# SCH_RP2350_Ucompute2_Rev1_1_2025-11-06.net
KiCad netlist of a schematic drawn in EasyEDA
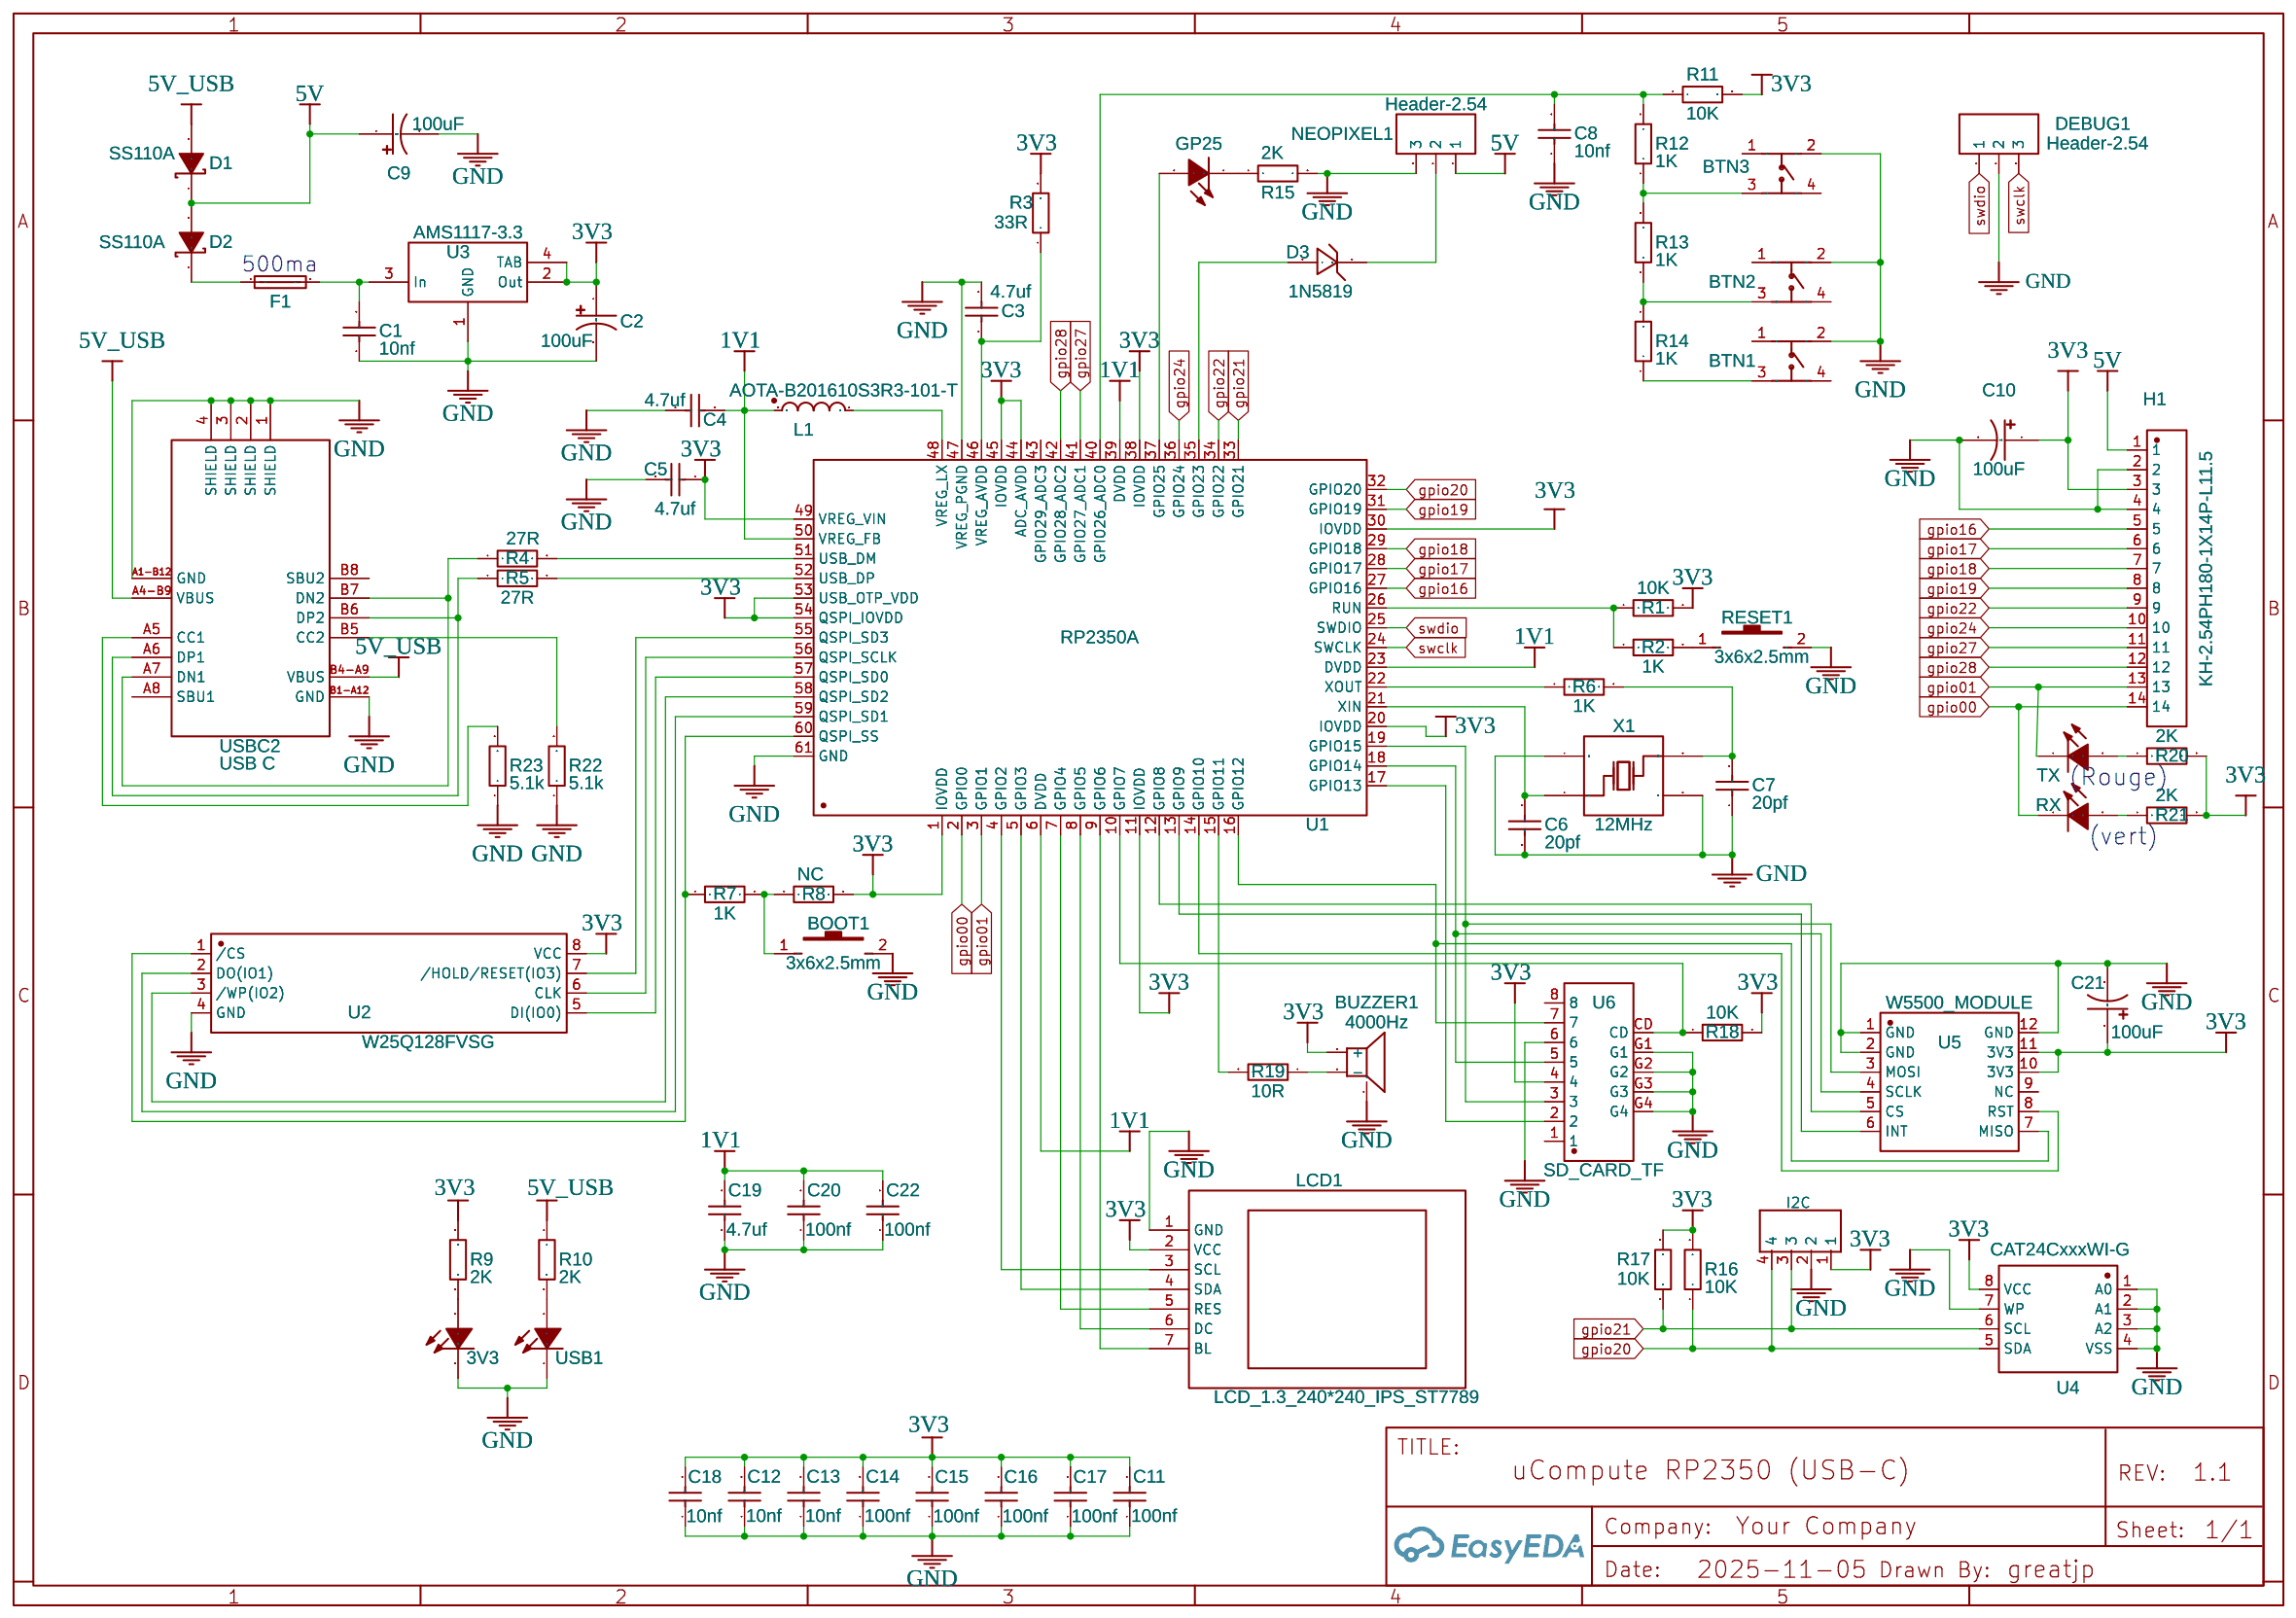
[diagram p0: schematic sheet]

(export (version "E")
  (design (tool "Eeschema 10.0.6"))
  (components
    (comp (ref "3V3")
      (value "XL-1206QPC")
      (fields (field (name "Manufacturer") "LCSC"))
      (libsource (lib "") (part "XL-1206QPC"))
    )
    (comp (ref "BOOT1")
      (value "3x6x2.5mm")
      (fields (field (name "Manufacturer") "ReliaPro"))
      (libsource (lib "") (part "3x6x2.5mm"))
    )
    (comp (ref "BTN1")
      (value "TC-1102-A-J-R")
      (fields (field (name "Manufacturer") "XKB Connectivity(中国星坤)"))
      (libsource (lib "") (part "TC-1102-A-J-R"))
    )
    (comp (ref "BTN2")
      (value "TC-1102-A-J-R")
      (fields (field (name "Manufacturer") "XKB Connectivity(中国星坤)"))
      (libsource (lib "") (part "TC-1102-A-J-R"))
    )
    (comp (ref "BTN3")
      (value "TC-1102-A-J-R")
      (fields (field (name "Manufacturer") "XKB Connectivity(中国星坤)"))
      (libsource (lib "") (part "TC-1102-A-J-R"))
    )
    (comp (ref "BUZZER1")
      (value "4000Hz")
      (fields (field (name "Manufacturer Part") "MLT-5030") (field (name "Manufacturer") "华能"))
      (libsource (lib "") (part "MLT-5030"))
    )
    (comp (ref "C1")
      (value "10nf")
      (fields (field (name "Manufacturer Part") "0805CG220J500NT") (field (name "Manufacturer") "FH"))
      (libsource (lib "") (part "0805CG220J500NT"))
    )
    (comp (ref "C2")
      (value "100uF")
      (fields
        (field (name "Manufacturer Part") "TLJA107M010R1400")
        (field (name "Manufacturer") "Kyocera AVX")
      )
      (libsource (lib "") (part "TLJA107M010R1400_3"))
    )
    (comp (ref "C3")
      (value "4.7uf")
      (fields (field (name "Manufacturer Part") "0805CG220J500NT") (field (name "Manufacturer") "FH"))
      (libsource (lib "") (part "0805CG220J500NT"))
    )
    (comp (ref "C4")
      (value "4.7uf")
      (fields (field (name "Manufacturer Part") "0805CG220J500NT") (field (name "Manufacturer") "FH"))
      (libsource (lib "") (part "0805CG220J500NT_1"))
    )
    (comp (ref "C5")
      (value "4.7uf")
      (fields (field (name "Manufacturer Part") "0805CG220J500NT") (field (name "Manufacturer") "FH"))
      (libsource (lib "") (part "0805CG220J500NT_1"))
    )
    (comp (ref "C6")
      (value "20pf")
      (fields (field (name "Manufacturer Part") "0805CG220J500NT") (field (name "Manufacturer") "FH"))
      (libsource (lib "") (part "0805CG220J500NT"))
    )
    (comp (ref "C7")
      (value "20pf")
      (fields (field (name "Manufacturer Part") "0805CG220J500NT") (field (name "Manufacturer") "FH"))
      (libsource (lib "") (part "0805CG220J500NT"))
    )
    (comp (ref "C8")
      (value "10nf")
      (fields (field (name "Manufacturer Part") "0805CG220J500NT") (field (name "Manufacturer") "FH"))
      (libsource (lib "") (part "0805CG220J500NT"))
    )
    (comp (ref "C9")
      (value "100uF")
      (fields
        (field (name "Manufacturer Part") "TLJA107M010R1400")
        (field (name "Manufacturer") "Kyocera AVX")
      )
      (libsource (lib "") (part "TLJA107M010R1400_2"))
    )
    (comp (ref "C10")
      (value "100uF")
      (fields
        (field (name "Manufacturer Part") "TLJA107M010R1400")
        (field (name "Manufacturer") "Kyocera AVX")
      )
      (libsource (lib "") (part "TLJA107M010R1400"))
    )
    (comp (ref "C11")
      (value "100nf")
      (fields (field (name "Manufacturer Part") "0805CG220J500NT") (field (name "Manufacturer") "FH"))
      (libsource (lib "") (part "0805CG220J500NT"))
    )
    (comp (ref "C12")
      (value "10nf")
      (fields (field (name "Manufacturer Part") "0805CG220J500NT") (field (name "Manufacturer") "FH"))
      (libsource (lib "") (part "0805CG220J500NT"))
    )
    (comp (ref "C13")
      (value "10nf")
      (fields (field (name "Manufacturer Part") "0805CG220J500NT") (field (name "Manufacturer") "FH"))
      (libsource (lib "") (part "0805CG220J500NT"))
    )
    (comp (ref "C14")
      (value "100nf")
      (fields (field (name "Manufacturer Part") "0805CG220J500NT") (field (name "Manufacturer") "FH"))
      (libsource (lib "") (part "0805CG220J500NT"))
    )
    (comp (ref "C15")
      (value "100nf")
      (fields (field (name "Manufacturer Part") "0805CG220J500NT") (field (name "Manufacturer") "FH"))
      (libsource (lib "") (part "0805CG220J500NT"))
    )
    (comp (ref "C16")
      (value "100nf")
      (fields (field (name "Manufacturer Part") "0805CG220J500NT") (field (name "Manufacturer") "FH"))
      (libsource (lib "") (part "0805CG220J500NT"))
    )
    (comp (ref "C17")
      (value "100nf")
      (fields (field (name "Manufacturer Part") "0805CG220J500NT") (field (name "Manufacturer") "FH"))
      (libsource (lib "") (part "0805CG220J500NT"))
    )
    (comp (ref "C18")
      (value "10nf")
      (fields (field (name "Manufacturer Part") "0805CG220J500NT") (field (name "Manufacturer") "FH"))
      (libsource (lib "") (part "0805CG220J500NT"))
    )
    (comp (ref "C19")
      (value "4.7uf")
      (fields (field (name "Manufacturer Part") "0805CG220J500NT") (field (name "Manufacturer") "FH"))
      (libsource (lib "") (part "0805CG220J500NT"))
    )
    (comp (ref "C20")
      (value "100nf")
      (fields (field (name "Manufacturer Part") "0805CG220J500NT") (field (name "Manufacturer") "FH"))
      (libsource (lib "") (part "0805CG220J500NT"))
    )
    (comp (ref "C21")
      (value "100uF")
      (fields
        (field (name "Manufacturer Part") "TLJA107M010R1400")
        (field (name "Manufacturer") "Kyocera AVX")
      )
      (libsource (lib "") (part "TLJA107M010R1400_1"))
    )
    (comp (ref "C22")
      (value "100nf")
      (fields (field (name "Manufacturer Part") "0805CG220J500NT") (field (name "Manufacturer") "FH"))
      (libsource (lib "") (part "0805CG220J500NT"))
    )
    (comp (ref "D1")
      (value "SS110A")
      (fields (field (name "Manufacturer") "Yangzhou Yangjie Elec Tech"))
      (libsource (lib "") (part "SS110A"))
    )
    (comp (ref "D2")
      (value "SS110A")
      (fields (field (name "Manufacturer") "Yangzhou Yangjie Elec Tech"))
      (libsource (lib "") (part "SS110A"))
    )
    (comp (ref "D3")
      (value "1N5819")
      (fields (field (name "Manufacturer Part") "1N4148D"))
      (libsource (lib "") (part "1N4148D"))
    )
    (comp (ref "DEBUG1")
      (value "Header-2.54")
      (fields (field (name "Manufacturer Part") "2.54-1*3P针") (field (name "Manufacturer") "BOOMELE(博穆精密)"))
      (libsource (lib "") (part "Header-Male-2.54_1x3_1"))
    )
    (comp (ref "F1")
      (value "FUSE1206")
      (fields (field (name "Manufacturer Part") "D22051903536_fuse1206"))
      (libsource (lib "") (part "D22051903536_FUSE1206"))
    )
    (comp (ref "GP25")
      (value "XL-1206QPC")
      (fields (field (name "Manufacturer") "LCSC"))
      (libsource (lib "") (part "XL-1206QPC_4"))
    )
    (comp (ref "H1")
      (value "KH-2.54PH180-1X14P-L11.5")
      (fields (field (name "Manufacturer") "kinghelm(金航标)"))
      (libsource (lib "") (part "KH-2.54PH180-1X14P-L11.5"))
    )
    (comp (ref "I2C") (value "I2C") (libsource (lib "") (part "Unknown_905_-191")))
    (comp (ref "L1")
      (value "AOTA-B201610S3R3-101-T")
      (fields (field (name "Manufacturer") "ABRACON"))
      (libsource (lib "") (part "AOTA-B201610S3R3-101-T"))
    )
    (comp (ref "LCD1")
      (value "LCD_1.3_240*240_IPS_ST7789")
      (libsource (lib "") (part "LCD_1.3_240*240_IPS_ST7789"))
    )
    (comp (ref "NEOPIXEL1")
      (value "Header-2.54")
      (fields (field (name "Manufacturer Part") "2.54-1*3P针") (field (name "Manufacturer") "BOOMELE(博穆精密)"))
      (libsource (lib "") (part "Header-Male-2.54_1x3"))
    )
    (comp (ref "R1")
      (value "10K")
      (fields (field (name "Manufacturer Part") "RC0805DR-071KL") (field (name "Manufacturer") "YAGEO(国巨)"))
      (libsource (lib "") (part "RC0805DR-071KL_1"))
    )
    (comp (ref "R2")
      (value "1K")
      (fields (field (name "Manufacturer Part") "RC0805DR-071KL") (field (name "Manufacturer") "YAGEO(国巨)"))
      (libsource (lib "") (part "RC0805DR-071KL_1"))
    )
    (comp (ref "R3")
      (value "33R")
      (fields (field (name "Manufacturer Part") "RC0805DR-071KL") (field (name "Manufacturer") "YAGEO(国巨)"))
      (libsource (lib "") (part "RC0805DR-071KL"))
    )
    (comp (ref "R4")
      (value "27R")
      (fields (field (name "Manufacturer Part") "RC0805DR-071KL") (field (name "Manufacturer") "YAGEO(国巨)"))
      (libsource (lib "") (part "RC0805DR-071KL_1"))
    )
    (comp (ref "R5")
      (value "27R")
      (fields (field (name "Manufacturer Part") "RC0805DR-071KL") (field (name "Manufacturer") "YAGEO(国巨)"))
      (libsource (lib "") (part "RC0805DR-071KL_1"))
    )
    (comp (ref "R6")
      (value "1K")
      (fields (field (name "Manufacturer Part") "RC0805DR-071KL") (field (name "Manufacturer") "YAGEO(国巨)"))
      (libsource (lib "") (part "RC0805DR-071KL_1"))
    )
    (comp (ref "R7")
      (value "1K")
      (fields (field (name "Manufacturer Part") "RC0805DR-071KL") (field (name "Manufacturer") "YAGEO(国巨)"))
      (libsource (lib "") (part "RC0805DR-071KL_1"))
    )
    (comp (ref "R8")
      (value "NC")
      (fields (field (name "Manufacturer Part") "RC0805DR-071KL") (field (name "Manufacturer") "YAGEO(国巨)"))
      (libsource (lib "") (part "RC0805DR-071KL_1"))
    )
    (comp (ref "R9")
      (value "2K")
      (fields (field (name "Manufacturer Part") "RC0805DR-071KL") (field (name "Manufacturer") "YAGEO(国巨)"))
      (libsource (lib "") (part "RC0805DR-071KL"))
    )
    (comp (ref "R10")
      (value "2K")
      (fields (field (name "Manufacturer Part") "RC0805DR-071KL") (field (name "Manufacturer") "YAGEO(国巨)"))
      (libsource (lib "") (part "RC0805DR-071KL_3"))
    )
    (comp (ref "R11")
      (value "10K")
      (fields (field (name "Manufacturer Part") "RC0805DR-071KL") (field (name "Manufacturer") "YAGEO(国巨)"))
      (libsource (lib "") (part "RC0805DR-071KL_1"))
    )
    (comp (ref "R12")
      (value "1K")
      (fields (field (name "Manufacturer Part") "RC0805DR-071KL") (field (name "Manufacturer") "YAGEO(国巨)"))
      (libsource (lib "") (part "RC0805DR-071KL"))
    )
    (comp (ref "R13")
      (value "1K")
      (fields (field (name "Manufacturer Part") "RC0805DR-071KL") (field (name "Manufacturer") "YAGEO(国巨)"))
      (libsource (lib "") (part "RC0805DR-071KL"))
    )
    (comp (ref "R14")
      (value "1K")
      (fields (field (name "Manufacturer Part") "RC0805DR-071KL") (field (name "Manufacturer") "YAGEO(国巨)"))
      (libsource (lib "") (part "RC0805DR-071KL"))
    )
    (comp (ref "R15")
      (value "2K")
      (fields (field (name "Manufacturer Part") "RC0805DR-071KL") (field (name "Manufacturer") "YAGEO(国巨)"))
      (libsource (lib "") (part "RC0805DR-071KL_1"))
    )
    (comp (ref "R16")
      (value "10K")
      (fields (field (name "Manufacturer Part") "RC0805DR-071KL") (field (name "Manufacturer") "YAGEO(国巨)"))
      (libsource (lib "") (part "RC0805DR-071KL"))
    )
    (comp (ref "R17")
      (value "10K")
      (fields (field (name "Manufacturer Part") "RC0805DR-071KL") (field (name "Manufacturer") "YAGEO(国巨)"))
      (libsource (lib "") (part "RC0805DR-071KL"))
    )
    (comp (ref "R18")
      (value "10K")
      (fields (field (name "Manufacturer Part") "RC0805DR-071KL") (field (name "Manufacturer") "YAGEO(国巨)"))
      (libsource (lib "") (part "RC0805DR-071KL_1"))
    )
    (comp (ref "R19")
      (value "10R")
      (fields (field (name "Manufacturer Part") "RC0805DR-071KL") (field (name "Manufacturer") "YAGEO(国巨)"))
      (libsource (lib "") (part "RC0805DR-071KL_2"))
    )
    (comp (ref "R20")
      (value "2K")
      (fields (field (name "Manufacturer Part") "RC0805DR-071KL") (field (name "Manufacturer") "YAGEO(国巨)"))
      (libsource (lib "") (part "RC0805DR-071KL_1"))
    )
    (comp (ref "R21")
      (value "2K")
      (fields (field (name "Manufacturer Part") "RC0805DR-071KL") (field (name "Manufacturer") "YAGEO(国巨)"))
      (libsource (lib "") (part "RC0805DR-071KL_1"))
    )
    (comp (ref "R22")
      (value "5.1k")
      (fields (field (name "Manufacturer Part") "RC0805DR-071KL") (field (name "Manufacturer") "YAGEO(国巨)"))
      (libsource (lib "") (part "RC0805DR-071KL"))
    )
    (comp (ref "R23")
      (value "5.1k")
      (fields (field (name "Manufacturer Part") "RC0805DR-071KL") (field (name "Manufacturer") "YAGEO(国巨)"))
      (libsource (lib "") (part "RC0805DR-071KL"))
    )
    (comp (ref "RESET1")
      (value "3x6x2.5mm")
      (fields (field (name "Manufacturer") "ReliaPro"))
      (libsource (lib "") (part "3x6x2.5mm_1"))
    )
    (comp (ref "RX1")
      (value "RX")
      (fields (field (name "Manufacturer Part") "XL-1206QPC") (field (name "Manufacturer") "LCSC"))
      (libsource (lib "") (part "XL-1206QPC_3"))
    )
    (comp (ref "TX1")
      (value "TX")
      (fields (field (name "Manufacturer Part") "XL-1206QPC") (field (name "Manufacturer") "LCSC"))
      (libsource (lib "") (part "XL-1206QPC_1"))
    )
    (comp (ref "U1")
      (value "RP2350A")
      (fields (field (name "Manufacturer") "Raspberry Pi(树莓派)"))
      (libsource (lib "") (part "RP2350A_C42411118"))
    )
    (comp (ref "U2") (value "W25Q128FVSG") (libsource (lib "") (part "W25Q128FVSG")))
    (comp (ref "U3")
      (value "AMS1117-3.3")
      (fields (field (name "Manufacturer Part") "AMS1117-5.0") (field (name "Manufacturer") "SK"))
      (libsource (lib "") (part "AMS1117-5.0_C165483"))
    )
    (comp (ref "U4") (value "CAT24CxxxWI-G") (libsource (lib "") (part "CAT24C256WI-G")))
    (comp (ref "U5") (value "W5500_MODULE") (libsource (lib "") (part "W5500_MODULE")))
    (comp (ref "U6")
      (value "SD_CARD_TF")
      (fields (field (name "Manufacturer Part") "SD_Card_TF"))
      (libsource (lib "") (part "SD_CARD_TF"))
    )
    (comp (ref "USB1")
      (value "XL-1206QPC")
      (fields (field (name "Manufacturer") "LCSC"))
      (libsource (lib "") (part "XL-1206QPC_2"))
    )
    (comp (ref "USBC2")
      (value "USB C")
      (fields (field (name "Manufacturer Part") "MC-311D") (field (name "Manufacturer") "SOFNG"))
      (libsource (lib "") (part "USB C"))
    )
    (comp (ref "X1")
      (value "12MHz")
      (fields
        (field (name "Manufacturer Part") "TSX-3225 12MHz 20pF 30ppm")
        (field (name "Manufacturer") "EPSON")
      )
      (libsource (lib "") (part "TSX-3225 12MHz 20pF 30ppm"))
    )
  )
  (nets
    (net (code "1") (name "1V1") (class "Default")
      (node (ref "C19") (pin "2") (pinfunction "2_2") (pintype "input"))
      (node (ref "C20") (pin "2") (pinfunction "2_2") (pintype "input"))
      (node (ref "C22") (pin "2") (pinfunction "2_2") (pintype "input"))
      (node (ref "C4") (pin "1") (pinfunction "1_1") (pintype "input"))
      (node (ref "L1") (pin "2") (pinfunction "2_2") (pintype "unspecified"))
      (node (ref "U1") (pin "23") (pinfunction "DVDD_23") (pintype "unspecified"))
      (node (ref "U1") (pin "39") (pinfunction "DVDD_39") (pintype "unspecified"))
      (node (ref "U1") (pin "50") (pinfunction "VREG_FB_50") (pintype "unspecified"))
      (node (ref "U1") (pin "6") (pinfunction "DVDD_6") (pintype "unspecified"))
    )
    (net (code "2") (name "3V3") (class "Default")
      (node (ref "BUZZER1") (pin "2") (pinfunction "+_2") (pintype "unspecified"))
      (node (ref "C10") (pin "1") (pinfunction "1_1") (pintype "unspecified"))
      (node (ref "C11") (pin "2") (pinfunction "2_2") (pintype "input"))
      (node (ref "C12") (pin "2") (pinfunction "2_2") (pintype "input"))
      (node (ref "C13") (pin "2") (pinfunction "2_2") (pintype "input"))
      (node (ref "C14") (pin "2") (pinfunction "2_2") (pintype "input"))
      (node (ref "C15") (pin "2") (pinfunction "2_2") (pintype "input"))
      (node (ref "C16") (pin "2") (pinfunction "2_2") (pintype "input"))
      (node (ref "C17") (pin "2") (pinfunction "2_2") (pintype "input"))
      (node (ref "C18") (pin "2") (pinfunction "2_2") (pintype "input"))
      (node (ref "C2") (pin "1") (pinfunction "1_1") (pintype "unspecified"))
      (node (ref "C21") (pin "1") (pinfunction "1_1") (pintype "unspecified"))
      (node (ref "C5") (pin "1") (pinfunction "1_1") (pintype "input"))
      (node (ref "H1") (pin "3") (pinfunction "3_3") (pintype "unspecified"))
      (node (ref "I2C") (pin "1") (pinfunction "1_1") (pintype "bidirectional"))
      (node (ref "LCD1") (pin "2") (pinfunction "VCC_2") (pintype "unspecified"))
      (node (ref "R1") (pin "2") (pinfunction "2_2") (pintype "unspecified"))
      (node (ref "R11") (pin "2") (pinfunction "2_2") (pintype "unspecified"))
      (node (ref "R16") (pin "2") (pinfunction "2_2") (pintype "unspecified"))
      (node (ref "R17") (pin "2") (pinfunction "2_2") (pintype "unspecified"))
      (node (ref "R18") (pin "2") (pinfunction "2_2") (pintype "unspecified"))
      (node (ref "R20") (pin "2") (pinfunction "2_2") (pintype "unspecified"))
      (node (ref "R21") (pin "2") (pinfunction "2_2") (pintype "unspecified"))
      (node (ref "R3") (pin "2") (pinfunction "2_2") (pintype "unspecified"))
      (node (ref "R8") (pin "2") (pinfunction "2_2") (pintype "unspecified"))
      (node (ref "R9") (pin "2") (pinfunction "2_2") (pintype "unspecified"))
      (node (ref "U1") (pin "1") (pinfunction "IOVDD_1") (pintype "unspecified"))
      (node (ref "U1") (pin "11") (pinfunction "IOVDD_11") (pintype "unspecified"))
      (node (ref "U1") (pin "20") (pinfunction "IOVDD_20") (pintype "unspecified"))
      (node (ref "U1") (pin "30") (pinfunction "IOVDD_30") (pintype "unspecified"))
      (node (ref "U1") (pin "38") (pinfunction "IOVDD_38") (pintype "unspecified"))
      (node (ref "U1") (pin "44") (pinfunction "ADC_AVDD_44") (pintype "unspecified"))
      (node (ref "U1") (pin "45") (pinfunction "IOVDD_45") (pintype "unspecified"))
      (node (ref "U1") (pin "49") (pinfunction "VREG_VIN_49") (pintype "unspecified"))
      (node (ref "U1") (pin "53") (pinfunction "USB_OTP_VDD_53") (pintype "unspecified"))
      (node (ref "U1") (pin "54") (pinfunction "QSPI_IOVDD_54") (pintype "unspecified"))
      (node (ref "U2") (pin "8") (pinfunction "VCC_8") (pintype "unspecified"))
      (node (ref "U3") (pin "2") (pinfunction "Out_2") (pintype "unspecified"))
      (node (ref "U3") (pin "4") (pinfunction "TAB_4") (pintype "unspecified"))
      (node (ref "U4") (pin "8") (pinfunction "VCC_8") (pintype "unspecified"))
      (node (ref "U5") (pin "10") (pinfunction "3V3_10") (pintype "unspecified"))
      (node (ref "U5") (pin "11") (pinfunction "3V3_11") (pintype "unspecified"))
      (node (ref "U6") (pin "4") (pinfunction "4_4") (pintype "unspecified"))
    )
    (net (code "3") (name "5V") (class "Default")
      (node (ref "C9") (pin "1") (pinfunction "1_1") (pintype "unspecified"))
      (node (ref "D1") (pin "2") (pinfunction "A_2") (pintype "unspecified"))
      (node (ref "D2") (pin "1") (pinfunction "K_1") (pintype "unspecified"))
      (node (ref "H1") (pin "1") (pinfunction "1_1") (pintype "unspecified"))
      (node (ref "NEOPIXEL1") (pin "1") (pinfunction "1_1") (pintype "input"))
    )
    (net (code "4") (name "5V_USB") (class "Default")
      (node (ref "D2") (pin "2") (pinfunction "A_2") (pintype "unspecified"))
      (node (ref "R10") (pin "1") (pinfunction "1_1") (pintype "unspecified"))
      (node (ref "USBC2") (pin "A4-B9") (pinfunction "VBUS_A4-B9") (pintype "unspecified"))
      (node (ref "USBC2") (pin "B4-A9") (pinfunction "VBUS_B4-A9") (pintype "unspecified"))
    )
    (net (code "5") (name "GND") (class "Default")
      (node (ref "3V3") (pin "1") (pinfunction "K_1") (pintype "unspecified"))
      (node (ref "BOOT1") (pin "2") (pinfunction "2_2") (pintype "input"))
      (node (ref "BTN1") (pin "2") (pinfunction "2_2") (pintype "unspecified"))
      (node (ref "BTN2") (pin "2") (pinfunction "2_2") (pintype "unspecified"))
      (node (ref "BTN3") (pin "2") (pinfunction "2_2") (pintype "unspecified"))
      (node (ref "BUZZER1") (pin "1") (pinfunction "NC_1") (pintype "unspecified"))
      (node (ref "C1") (pin "1") (pinfunction "1_1") (pintype "input"))
      (node (ref "C10") (pin "2") (pinfunction "2_2") (pintype "unspecified"))
      (node (ref "C11") (pin "1") (pinfunction "1_1") (pintype "input"))
      (node (ref "C12") (pin "1") (pinfunction "1_1") (pintype "input"))
      (node (ref "C13") (pin "1") (pinfunction "1_1") (pintype "input"))
      (node (ref "C14") (pin "1") (pinfunction "1_1") (pintype "input"))
      (node (ref "C15") (pin "1") (pinfunction "1_1") (pintype "input"))
      (node (ref "C16") (pin "1") (pinfunction "1_1") (pintype "input"))
      (node (ref "C17") (pin "1") (pinfunction "1_1") (pintype "input"))
      (node (ref "C18") (pin "1") (pinfunction "1_1") (pintype "input"))
      (node (ref "C19") (pin "1") (pinfunction "1_1") (pintype "input"))
      (node (ref "C2") (pin "2") (pinfunction "2_2") (pintype "unspecified"))
      (node (ref "C20") (pin "1") (pinfunction "1_1") (pintype "input"))
      (node (ref "C21") (pin "2") (pinfunction "2_2") (pintype "unspecified"))
      (node (ref "C22") (pin "1") (pinfunction "1_1") (pintype "input"))
      (node (ref "C3") (pin "2") (pinfunction "2_2") (pintype "input"))
      (node (ref "C4") (pin "2") (pinfunction "2_2") (pintype "input"))
      (node (ref "C5") (pin "2") (pinfunction "2_2") (pintype "input"))
      (node (ref "C6") (pin "1") (pinfunction "1_1") (pintype "input"))
      (node (ref "C7") (pin "1") (pinfunction "1_1") (pintype "input"))
      (node (ref "C8") (pin "1") (pinfunction "1_1") (pintype "input"))
      (node (ref "C9") (pin "2") (pinfunction "2_2") (pintype "unspecified"))
      (node (ref "DEBUG1") (pin "2") (pinfunction "2_2") (pintype "input"))
      (node (ref "H1") (pin "2") (pinfunction "2_2") (pintype "unspecified"))
      (node (ref "H1") (pin "4") (pinfunction "4_4") (pintype "unspecified"))
      (node (ref "I2C") (pin "2") (pinfunction "2_2") (pintype "bidirectional"))
      (node (ref "LCD1") (pin "1") (pinfunction "GND_1") (pintype "unspecified"))
      (node (ref "NEOPIXEL1") (pin "3") (pinfunction "3_3") (pintype "input"))
      (node (ref "R15") (pin "2") (pinfunction "2_2") (pintype "unspecified"))
      (node (ref "R22") (pin "1") (pinfunction "1_1") (pintype "unspecified"))
      (node (ref "R23") (pin "1") (pinfunction "1_1") (pintype "unspecified"))
      (node (ref "RESET1") (pin "2") (pinfunction "2_2") (pintype "input"))
      (node (ref "U1") (pin "47") (pinfunction "VREG_PGND_47") (pintype "unspecified"))
      (node (ref "U1") (pin "61") (pinfunction "GND_61") (pintype "unspecified"))
      (node (ref "U2") (pin "4") (pinfunction "GND_4") (pintype "unspecified"))
      (node (ref "U3") (pin "1") (pinfunction "GND_1") (pintype "unspecified"))
      (node (ref "U4") (pin "1") (pinfunction "A0_1") (pintype "unspecified"))
      (node (ref "U4") (pin "2") (pinfunction "A1_2") (pintype "unspecified"))
      (node (ref "U4") (pin "3") (pinfunction "A2_3") (pintype "unspecified"))
      (node (ref "U4") (pin "4") (pinfunction "VSS_4") (pintype "unspecified"))
      (node (ref "U4") (pin "7") (pinfunction "WP_7") (pintype "unspecified"))
      (node (ref "U5") (pin "1") (pinfunction "GND_1") (pintype "unspecified"))
      (node (ref "U5") (pin "12") (pinfunction "GND_12") (pintype "unspecified"))
      (node (ref "U5") (pin "2") (pinfunction "GND_2") (pintype "unspecified"))
      (node (ref "U6") (pin "6") (pinfunction "6_6") (pintype "unspecified"))
      (node (ref "U6") (pin "G1") (pinfunction "G1_G1") (pintype "unspecified"))
      (node (ref "U6") (pin "G2") (pinfunction "G2_G2") (pintype "unspecified"))
      (node (ref "U6") (pin "G3") (pinfunction "G3_G3") (pintype "unspecified"))
      (node (ref "U6") (pin "G4") (pinfunction "G4_G4") (pintype "unspecified"))
      (node (ref "USB1") (pin "1") (pinfunction "K_1") (pintype "unspecified"))
      (node (ref "USBC2") (pin "1") (pinfunction "SHIELD_1") (pintype "unspecified"))
      (node (ref "USBC2") (pin "2") (pinfunction "SHIELD_2") (pintype "unspecified"))
      (node (ref "USBC2") (pin "3") (pinfunction "SHIELD_3") (pintype "unspecified"))
      (node (ref "USBC2") (pin "4") (pinfunction "SHIELD_4") (pintype "unspecified"))
      (node (ref "USBC2") (pin "A1-B12") (pinfunction "GND_A1-B12") (pintype "unspecified"))
      (node (ref "USBC2") (pin "B1-A12") (pinfunction "GND_B1-A12") (pintype "unspecified"))
      (node (ref "X1") (pin "2") (pinfunction "NC_2") (pintype "input"))
      (node (ref "X1") (pin "4") (pinfunction "NC_4") (pintype "input"))
    )
    (net (code "6") (name "Net-(3V3-A)") (class "Default")
      (node (ref "3V3") (pin "2") (pinfunction "A_2") (pintype "unspecified"))
      (node (ref "R9") (pin "1") (pinfunction "1_1") (pintype "unspecified"))
    )
    (net (code "7") (name "Net-(BOOT1-Pad1)") (class "Default")
      (node (ref "BOOT1") (pin "1") (pinfunction "1_1") (pintype "input"))
      (node (ref "R7") (pin "2") (pinfunction "2_2") (pintype "unspecified"))
      (node (ref "R8") (pin "1") (pinfunction "1_1") (pintype "unspecified"))
    )
    (net (code "8") (name "Net-(BTN1-Pad3)") (class "Default")
      (node (ref "BTN1") (pin "3") (pinfunction "3_3") (pintype "unspecified"))
      (node (ref "R14") (pin "1") (pinfunction "1_1") (pintype "unspecified"))
    )
    (net (code "9") (name "Net-(BTN2-Pad3)") (class "Default")
      (node (ref "BTN2") (pin "3") (pinfunction "3_3") (pintype "unspecified"))
      (node (ref "R13") (pin "1") (pinfunction "1_1") (pintype "unspecified"))
      (node (ref "R14") (pin "2") (pinfunction "2_2") (pintype "unspecified"))
    )
    (net (code "10") (name "Net-(BTN3-Pad3)") (class "Default")
      (node (ref "BTN3") (pin "3") (pinfunction "3_3") (pintype "unspecified"))
      (node (ref "R12") (pin "1") (pinfunction "1_1") (pintype "unspecified"))
      (node (ref "R13") (pin "2") (pinfunction "2_2") (pintype "unspecified"))
    )
    (net (code "11") (name "Net-(BUZZER1--)") (class "Default")
      (node (ref "BUZZER1") (pin "3") (pinfunction "-_3") (pintype "unspecified"))
      (node (ref "R19") (pin "1") (pinfunction "1_1") (pintype "unspecified"))
    )
    (net (code "12") (name "Net-(D1-K)") (class "Default")
      (node (ref "D1") (pin "1") (pinfunction "K_1") (pintype "unspecified"))
      (node (ref "F1") (pin "1") (pinfunction "1_1") (pintype "unspecified"))
    )
    (net (code "13") (name "Net-(D3-A)") (class "Default")
      (node (ref "D3") (pin "2") (pinfunction "A_2") (pintype "unspecified"))
      (node (ref "U1") (pin "35") (pinfunction "GPIO23_35") (pintype "unspecified"))
    )
    (net (code "14") (name "Net-(D3-C)") (class "Default")
      (node (ref "D3") (pin "1") (pinfunction "C_1") (pintype "unspecified"))
      (node (ref "NEOPIXEL1") (pin "2") (pinfunction "2_2") (pintype "input"))
    )
    (net (code "15") (name "Net-(GP25-A)") (class "Default")
      (node (ref "GP25") (pin "2") (pinfunction "A_2") (pintype "unspecified"))
      (node (ref "U1") (pin "37") (pinfunction "GPIO25_37") (pintype "unspecified"))
    )
    (net (code "16") (name "Net-(GP25-K)") (class "Default")
      (node (ref "GP25") (pin "1") (pinfunction "K_1") (pintype "unspecified"))
      (node (ref "R15") (pin "1") (pinfunction "1_1") (pintype "unspecified"))
    )
    (net (code "17") (name "Net-(LCD1-BL)") (class "Default")
      (node (ref "LCD1") (pin "7") (pinfunction "BL_7") (pintype "unspecified"))
      (node (ref "U1") (pin "9") (pinfunction "GPIO6_9") (pintype "unspecified"))
    )
    (net (code "18") (name "Net-(LCD1-DC)") (class "Default")
      (node (ref "LCD1") (pin "6") (pinfunction "DC_6") (pintype "unspecified"))
      (node (ref "U1") (pin "8") (pinfunction "GPIO5_8") (pintype "unspecified"))
    )
    (net (code "19") (name "Net-(LCD1-RES)") (class "Default")
      (node (ref "LCD1") (pin "5") (pinfunction "RES_5") (pintype "unspecified"))
      (node (ref "U1") (pin "7") (pinfunction "GPIO4_7") (pintype "unspecified"))
    )
    (net (code "20") (name "Net-(LCD1-SCL)") (class "Default")
      (node (ref "LCD1") (pin "3") (pinfunction "SCL_3") (pintype "unspecified"))
      (node (ref "U1") (pin "4") (pinfunction "GPIO2_4") (pintype "unspecified"))
    )
    (net (code "21") (name "Net-(LCD1-SDA)") (class "Default")
      (node (ref "LCD1") (pin "4") (pinfunction "SDA_4") (pintype "unspecified"))
      (node (ref "U1") (pin "5") (pinfunction "GPIO3_5") (pintype "unspecified"))
    )
    (net (code "22") (name "Net-(R2-Pad2)") (class "Default")
      (node (ref "R2") (pin "2") (pinfunction "2_2") (pintype "unspecified"))
      (node (ref "RESET1") (pin "1") (pinfunction "1_1") (pintype "input"))
    )
    (net (code "23") (name "Net-(RX1-A)") (class "Default")
      (node (ref "R21") (pin "1") (pinfunction "1_1") (pintype "unspecified"))
      (node (ref "RX1") (pin "2") (pinfunction "A_2") (pintype "unspecified"))
    )
    (net (code "24") (name "Net-(TX1-A)") (class "Default")
      (node (ref "R20") (pin "1") (pinfunction "1_1") (pintype "unspecified"))
      (node (ref "TX1") (pin "2") (pinfunction "A_2") (pintype "unspecified"))
    )
    (net (code "25") (name "Net-(U1-GPIO7)") (class "Default")
      (node (ref "R18") (pin "1") (pinfunction "1_1") (pintype "unspecified"))
      (node (ref "U1") (pin "10") (pinfunction "GPIO7_10") (pintype "unspecified"))
      (node (ref "U6") (pin "CD") (pinfunction "CD_CD") (pintype "unspecified"))
    )
    (net (code "26") (name "Net-(U1-GPIO8)") (class "Default")
      (node (ref "U1") (pin "12") (pinfunction "GPIO8_12") (pintype "unspecified"))
      (node (ref "U5") (pin "5") (pinfunction "CS_5") (pintype "unspecified"))
    )
    (net (code "27") (name "Net-(U1-GPIO9)") (class "Default")
      (node (ref "U1") (pin "13") (pinfunction "GPIO9_13") (pintype "unspecified"))
      (node (ref "U5") (pin "6") (pinfunction "INT_6") (pintype "unspecified"))
    )
    (net (code "28") (name "Net-(U1-GPIO10)") (class "Default")
      (node (ref "U1") (pin "14") (pinfunction "GPIO10_14") (pintype "unspecified"))
      (node (ref "U5") (pin "8") (pinfunction "RST_8") (pintype "unspecified"))
    )
    (net (code "29") (name "Net-(U1-GPIO11)") (class "Default")
      (node (ref "R19") (pin "2") (pinfunction "2_2") (pintype "unspecified"))
      (node (ref "U1") (pin "15") (pinfunction "GPIO11_15") (pintype "unspecified"))
    )
    (net (code "30") (name "Net-(U1-GPIO12)") (class "Default")
      (node (ref "U1") (pin "16") (pinfunction "GPIO12_16") (pintype "unspecified"))
      (node (ref "U5") (pin "7") (pinfunction "MISO_7") (pintype "unspecified"))
      (node (ref "U6") (pin "7") (pinfunction "7_7") (pintype "unspecified"))
    )
    (net (code "31") (name "Net-(U1-GPIO13)") (class "Default")
      (node (ref "U1") (pin "17") (pinfunction "GPIO13_17") (pintype "unspecified"))
      (node (ref "U6") (pin "2") (pinfunction "2_2") (pintype "unspecified"))
    )
    (net (code "32") (name "Net-(U1-GPIO14)") (class "Default")
      (node (ref "U1") (pin "18") (pinfunction "GPIO14_18") (pintype "unspecified"))
      (node (ref "U5") (pin "4") (pinfunction "SCLK_4") (pintype "unspecified"))
      (node (ref "U6") (pin "5") (pinfunction "5_5") (pintype "unspecified"))
    )
    (net (code "33") (name "Net-(U1-GPIO15)") (class "Default")
      (node (ref "U1") (pin "19") (pinfunction "GPIO15_19") (pintype "unspecified"))
      (node (ref "U5") (pin "3") (pinfunction "MOSI_3") (pintype "unspecified"))
      (node (ref "U6") (pin "3") (pinfunction "3_3") (pintype "unspecified"))
    )
    (net (code "34") (name "Net-(U1-GPIO26_ADC0)") (class "Default")
      (node (ref "C8") (pin "2") (pinfunction "2_2") (pintype "input"))
      (node (ref "R11") (pin "1") (pinfunction "1_1") (pintype "unspecified"))
      (node (ref "R12") (pin "2") (pinfunction "2_2") (pintype "unspecified"))
      (node (ref "U1") (pin "40") (pinfunction "GPIO26_ADC0_40") (pintype "unspecified"))
    )
    (net (code "35") (name "Net-(U1-QSPI_SCLK)") (class "Default")
      (node (ref "U1") (pin "56") (pinfunction "QSPI_SCLK_56") (pintype "unspecified"))
      (node (ref "U2") (pin "6") (pinfunction "CLK_6") (pintype "unspecified"))
    )
    (net (code "36") (name "Net-(U1-QSPI_SD0)") (class "Default")
      (node (ref "U1") (pin "57") (pinfunction "QSPI_SD0_57") (pintype "unspecified"))
      (node (ref "U2") (pin "5") (pinfunction "DI(IO0)_5") (pintype "unspecified"))
    )
    (net (code "37") (name "Net-(U1-QSPI_SD1)") (class "Default")
      (node (ref "U1") (pin "59") (pinfunction "QSPI_SD1_59") (pintype "unspecified"))
      (node (ref "U2") (pin "2") (pinfunction "DO(IO1)_2") (pintype "unspecified"))
    )
    (net (code "38") (name "Net-(U1-QSPI_SD2)") (class "Default")
      (node (ref "U1") (pin "58") (pinfunction "QSPI_SD2_58") (pintype "unspecified"))
      (node (ref "U2") (pin "3") (pinfunction "/WP(IO2)_3") (pintype "unspecified"))
    )
    (net (code "39") (name "Net-(U1-QSPI_SD3)") (class "Default")
      (node (ref "U1") (pin "55") (pinfunction "QSPI_SD3_55") (pintype "unspecified"))
      (node (ref "U2") (pin "7") (pinfunction "/HOLD/RESET(IO3)_7") (pintype "unspecified"))
    )
    (net (code "40") (name "Net-(U1-QSPI_SS)") (class "Default")
      (node (ref "R7") (pin "1") (pinfunction "1_1") (pintype "unspecified"))
      (node (ref "U1") (pin "60") (pinfunction "QSPI_SS_60") (pintype "unspecified"))
      (node (ref "U2") (pin "1") (pinfunction "/CS_1") (pintype "unspecified"))
    )
    (net (code "41") (name "Net-(U1-RUN)") (class "Default")
      (node (ref "R1") (pin "1") (pinfunction "1_1") (pintype "unspecified"))
      (node (ref "R2") (pin "1") (pinfunction "1_1") (pintype "unspecified"))
      (node (ref "U1") (pin "26") (pinfunction "RUN_26") (pintype "unspecified"))
    )
    (net (code "42") (name "Net-(U1-USB_DM)") (class "Default")
      (node (ref "R4") (pin "2") (pinfunction "2_2") (pintype "unspecified"))
      (node (ref "U1") (pin "51") (pinfunction "USB_DM_51") (pintype "unspecified"))
    )
    (net (code "43") (name "Net-(U1-USB_DP)") (class "Default")
      (node (ref "R5") (pin "2") (pinfunction "2_2") (pintype "unspecified"))
      (node (ref "U1") (pin "52") (pinfunction "USB_DP_52") (pintype "unspecified"))
    )
    (net (code "44") (name "Net-(U1-VREG_AVDD)") (class "Default")
      (node (ref "C3") (pin "1") (pinfunction "1_1") (pintype "input"))
      (node (ref "R3") (pin "1") (pinfunction "1_1") (pintype "unspecified"))
      (node (ref "U1") (pin "46") (pinfunction "VREG_AVDD_46") (pintype "unspecified"))
    )
    (net (code "45") (name "Net-(U1-VREG_LX)") (class "Default")
      (node (ref "L1") (pin "1") (pinfunction "1_1") (pintype "unspecified"))
      (node (ref "U1") (pin "48") (pinfunction "VREG_LX_48") (pintype "unspecified"))
    )
    (net (code "46") (name "Net-(U1-XIN)") (class "Default")
      (node (ref "C6") (pin "2") (pinfunction "2_2") (pintype "input"))
      (node (ref "U1") (pin "21") (pinfunction "XIN_21") (pintype "unspecified"))
      (node (ref "X1") (pin "1") (pinfunction "OSC1_1") (pintype "input"))
    )
    (net (code "47") (name "Net-(U1-XOUT)") (class "Default")
      (node (ref "R6") (pin "1") (pinfunction "1_1") (pintype "unspecified"))
      (node (ref "U1") (pin "22") (pinfunction "XOUT_22") (pintype "unspecified"))
    )
    (net (code "48") (name "Net-(U3-In)") (class "Default")
      (node (ref "C1") (pin "2") (pinfunction "2_2") (pintype "input"))
      (node (ref "F1") (pin "2") (pinfunction "2_2") (pintype "unspecified"))
      (node (ref "U3") (pin "3") (pinfunction "In_3") (pintype "unspecified"))
    )
    (net (code "49") (name "Net-(USB1-A)") (class "Default")
      (node (ref "R10") (pin "2") (pinfunction "2_2") (pintype "unspecified"))
      (node (ref "USB1") (pin "2") (pinfunction "A_2") (pintype "unspecified"))
    )
    (net (code "50") (name "Net-(USBC2-CC1)") (class "Default")
      (node (ref "R23") (pin "2") (pinfunction "2_2") (pintype "unspecified"))
      (node (ref "USBC2") (pin "A5") (pinfunction "CC1_A5") (pintype "unspecified"))
    )
    (net (code "51") (name "Net-(USBC2-CC2)") (class "Default")
      (node (ref "R22") (pin "2") (pinfunction "2_2") (pintype "unspecified"))
      (node (ref "USBC2") (pin "B5") (pinfunction "CC2_B5") (pintype "unspecified"))
    )
    (net (code "52") (name "Net-(USBC2-DN1)") (class "Default")
      (node (ref "R4") (pin "1") (pinfunction "1_1") (pintype "unspecified"))
      (node (ref "USBC2") (pin "A7") (pinfunction "DN1_A7") (pintype "unspecified"))
      (node (ref "USBC2") (pin "B7") (pinfunction "DN2_B7") (pintype "unspecified"))
    )
    (net (code "53") (name "Net-(USBC2-DP1)") (class "Default")
      (node (ref "R5") (pin "1") (pinfunction "1_1") (pintype "unspecified"))
      (node (ref "USBC2") (pin "A6") (pinfunction "DP1_A6") (pintype "unspecified"))
      (node (ref "USBC2") (pin "B6") (pinfunction "DP2_B6") (pintype "unspecified"))
    )
    (net (code "54") (name "Net-(X1-OSC2)") (class "Default")
      (node (ref "C7") (pin "2") (pinfunction "2_2") (pintype "input"))
      (node (ref "R6") (pin "2") (pinfunction "2_2") (pintype "unspecified"))
      (node (ref "X1") (pin "3") (pinfunction "OSC2_3") (pintype "input"))
    )
    (net (code "55") (name "gpio00") (class "Default")
      (node (ref "H1") (pin "14") (pinfunction "14_14") (pintype "unspecified"))
      (node (ref "RX1") (pin "1") (pinfunction "K_1") (pintype "unspecified"))
      (node (ref "U1") (pin "2") (pinfunction "GPIO0_2") (pintype "unspecified"))
    )
    (net (code "56") (name "gpio01") (class "Default")
      (node (ref "H1") (pin "13") (pinfunction "13_13") (pintype "unspecified"))
      (node (ref "TX1") (pin "1") (pinfunction "K_1") (pintype "unspecified"))
      (node (ref "U1") (pin "3") (pinfunction "GPIO1_3") (pintype "unspecified"))
    )
    (net (code "57") (name "gpio16") (class "Default")
      (node (ref "H1") (pin "5") (pinfunction "5_5") (pintype "unspecified"))
      (node (ref "U1") (pin "27") (pinfunction "GPIO16_27") (pintype "unspecified"))
    )
    (net (code "58") (name "gpio17") (class "Default")
      (node (ref "H1") (pin "6") (pinfunction "6_6") (pintype "unspecified"))
      (node (ref "U1") (pin "28") (pinfunction "GPIO17_28") (pintype "unspecified"))
    )
    (net (code "59") (name "gpio18") (class "Default")
      (node (ref "H1") (pin "7") (pinfunction "7_7") (pintype "unspecified"))
      (node (ref "U1") (pin "29") (pinfunction "GPIO18_29") (pintype "unspecified"))
    )
    (net (code "60") (name "gpio19") (class "Default")
      (node (ref "H1") (pin "8") (pinfunction "8_8") (pintype "unspecified"))
      (node (ref "U1") (pin "31") (pinfunction "GPIO19_31") (pintype "unspecified"))
    )
    (net (code "61") (name "gpio20") (class "Default")
      (node (ref "I2C") (pin "4") (pinfunction "4_4") (pintype "bidirectional"))
      (node (ref "R16") (pin "1") (pinfunction "1_1") (pintype "unspecified"))
      (node (ref "U1") (pin "32") (pinfunction "GPIO20_32") (pintype "unspecified"))
      (node (ref "U4") (pin "5") (pinfunction "SDA_5") (pintype "unspecified"))
    )
    (net (code "62") (name "gpio21") (class "Default")
      (node (ref "I2C") (pin "3") (pinfunction "3_3") (pintype "bidirectional"))
      (node (ref "R17") (pin "1") (pinfunction "1_1") (pintype "unspecified"))
      (node (ref "U1") (pin "33") (pinfunction "GPIO21_33") (pintype "unspecified"))
      (node (ref "U4") (pin "6") (pinfunction "SCL_6") (pintype "unspecified"))
    )
    (net (code "63") (name "gpio22") (class "Default")
      (node (ref "H1") (pin "9") (pinfunction "9_9") (pintype "unspecified"))
      (node (ref "U1") (pin "34") (pinfunction "GPIO22_34") (pintype "unspecified"))
    )
    (net (code "64") (name "gpio24") (class "Default")
      (node (ref "H1") (pin "10") (pinfunction "10_10") (pintype "unspecified"))
      (node (ref "U1") (pin "36") (pinfunction "GPIO24_36") (pintype "unspecified"))
    )
    (net (code "65") (name "gpio27") (class "Default")
      (node (ref "H1") (pin "11") (pinfunction "11_11") (pintype "unspecified"))
      (node (ref "U1") (pin "41") (pinfunction "GPIO27_ADC1_41") (pintype "unspecified"))
    )
    (net (code "66") (name "gpio28") (class "Default")
      (node (ref "H1") (pin "12") (pinfunction "12_12") (pintype "unspecified"))
      (node (ref "U1") (pin "42") (pinfunction "GPIO28_ADC2_42") (pintype "unspecified"))
    )
    (net (code "67") (name "swclk") (class "Default")
      (node (ref "DEBUG1") (pin "3") (pinfunction "3_3") (pintype "input"))
      (node (ref "U1") (pin "24") (pinfunction "SWCLK_24") (pintype "unspecified"))
    )
    (net (code "68") (name "swdio") (class "Default")
      (node (ref "DEBUG1") (pin "1") (pinfunction "1_1") (pintype "input"))
      (node (ref "U1") (pin "25") (pinfunction "SWDIO_25") (pintype "unspecified"))
    )
    (net (code "69") (name "unconnected-(BTN1-Pad1)") (class "Default")
      (node (ref "BTN1") (pin "1") (pinfunction "1_1") (pintype "unspecified"))
    )
    (net (code "70") (name "unconnected-(BTN1-Pad4)") (class "Default")
      (node (ref "BTN1") (pin "4") (pinfunction "4_4") (pintype "unspecified"))
    )
    (net (code "71") (name "unconnected-(BTN2-Pad1)") (class "Default")
      (node (ref "BTN2") (pin "1") (pinfunction "1_1") (pintype "unspecified"))
    )
    (net (code "72") (name "unconnected-(BTN2-Pad4)") (class "Default")
      (node (ref "BTN2") (pin "4") (pinfunction "4_4") (pintype "unspecified"))
    )
    (net (code "73") (name "unconnected-(BTN3-Pad1)") (class "Default")
      (node (ref "BTN3") (pin "1") (pinfunction "1_1") (pintype "unspecified"))
    )
    (net (code "74") (name "unconnected-(BTN3-Pad4)") (class "Default")
      (node (ref "BTN3") (pin "4") (pinfunction "4_4") (pintype "unspecified"))
    )
    (net (code "75") (name "unconnected-(U1-GPIO29_ADC3-Pad43)") (class "Default")
      (node (ref "U1") (pin "43") (pinfunction "GPIO29_ADC3_43") (pintype "unspecified"))
    )
    (net (code "76") (name "unconnected-(U5-NC-Pad9)") (class "Default")
      (node (ref "U5") (pin "9") (pinfunction "NC_9") (pintype "unspecified"))
    )
    (net (code "77") (name "unconnected-(U6-Pad1)") (class "Default")
      (node (ref "U6") (pin "1") (pinfunction "1_1") (pintype "unspecified"))
    )
    (net (code "78") (name "unconnected-(U6-Pad8)") (class "Default")
      (node (ref "U6") (pin "8") (pinfunction "8_8") (pintype "unspecified"))
    )
    (net (code "79") (name "unconnected-(USBC2-SBU1-PadA8)") (class "Default")
      (node (ref "USBC2") (pin "A8") (pinfunction "SBU1_A8") (pintype "unspecified"))
    )
    (net (code "80") (name "unconnected-(USBC2-SBU2-PadB8)") (class "Default")
      (node (ref "USBC2") (pin "B8") (pinfunction "SBU2_B8") (pintype "unspecified"))
    )
  )
)
